# 29_SmartSensor_HW_PGA_ver_0_0_1_PGA460_v.net
KiCad netlist of a schematic drawn in EAGLE
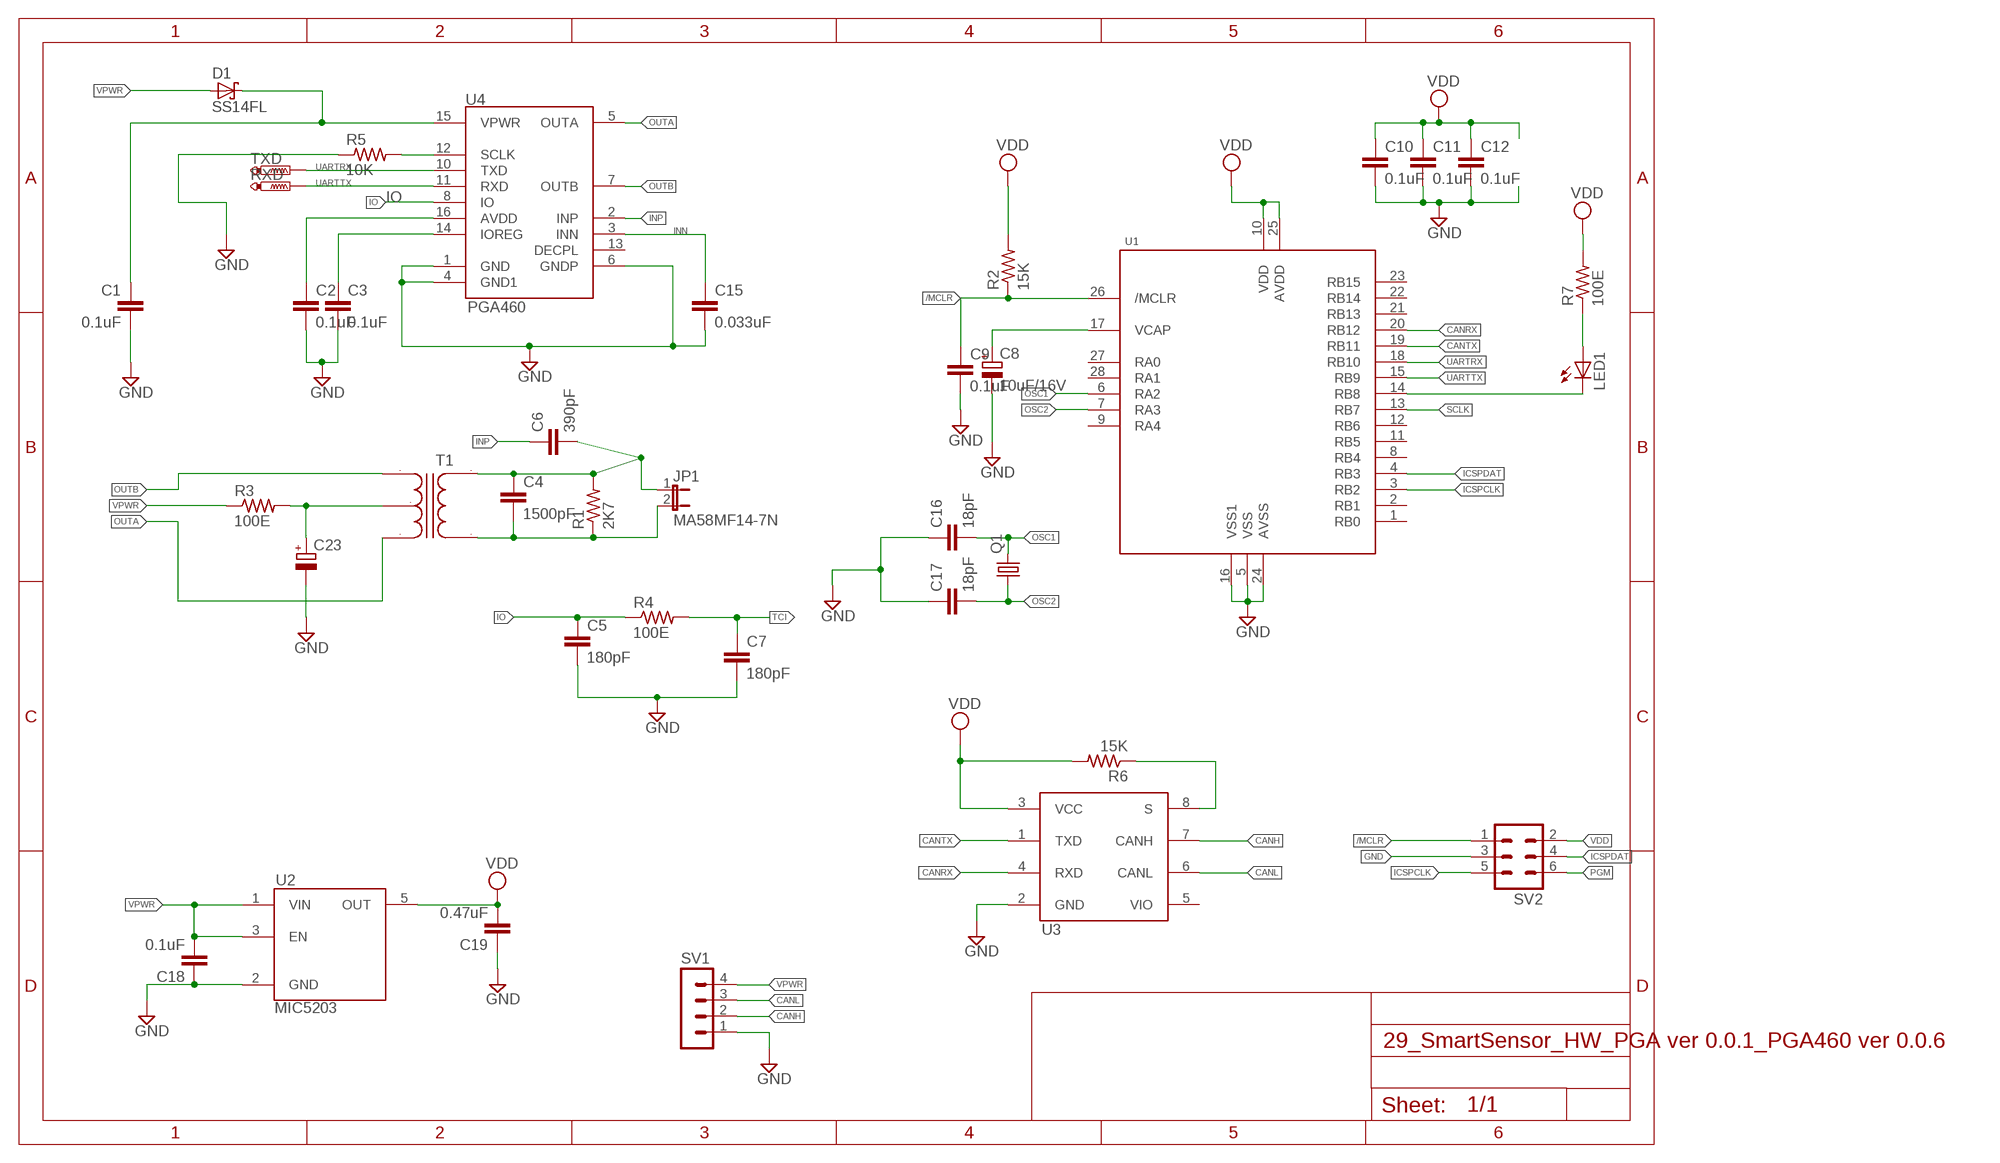
[diagram p0: schematic, sheet 1]

(export (version "E")
  (design (tool "Eeschema 10.0.6"))
  (components
    (comp (ref "C1")
      (value "0.1uF")
      (footprint "eagle-import:C0603K")
      (libsource (lib "eagle-import") (part "C-EUC0603K"))
    )
    (comp (ref "C2")
      (value "0.1uF")
      (footprint "eagle-import:C0603K")
      (libsource (lib "eagle-import") (part "C-EUC0603K"))
    )
    (comp (ref "C3")
      (value "0.1uF")
      (footprint "eagle-import:C0603K")
      (libsource (lib "eagle-import") (part "C-EUC0603K"))
    )
    (comp (ref "C4")
      (value "1500pF")
      (footprint "eagle-import:C0603K")
      (libsource (lib "eagle-import") (part "C-EUC0603K"))
    )
    (comp (ref "C5")
      (value "180pF")
      (footprint "eagle-import:C0603K")
      (libsource (lib "eagle-import") (part "C-EUC0603K"))
    )
    (comp (ref "C6")
      (value "390pF")
      (footprint "eagle-import:C0603K")
      (libsource (lib "eagle-import") (part "C-EUC0603K"))
    )
    (comp (ref "C7")
      (value "180pF")
      (footprint "eagle-import:C0603K")
      (libsource (lib "eagle-import") (part "C-EUC0603K"))
    )
    (comp (ref "C8")
      (value "10uF/16V")
      (footprint "eagle-import:B_3528-21R")
      (libsource (lib "eagle-import") (part "rcl_334_CPOL-EUB/3528-21R"))
    )
    (comp (ref "C9")
      (value "0.1uF")
      (footprint "eagle-import:C0603K")
      (libsource (lib "eagle-import") (part "rcl_334_C-EUC0603K"))
    )
    (comp (ref "C10")
      (value "0.1uF")
      (footprint "eagle-import:C0603K")
      (libsource (lib "eagle-import") (part "rcl_334_C-EUC0603K"))
    )
    (comp (ref "C11")
      (value "0.1uF")
      (footprint "eagle-import:C0603K")
      (libsource (lib "eagle-import") (part "rcl_334_C-EUC0603K"))
    )
    (comp (ref "C12")
      (value "0.1uF")
      (footprint "eagle-import:C0603K")
      (libsource (lib "eagle-import") (part "rcl_334_C-EUC0603K"))
    )
    (comp (ref "C15")
      (value "0.033uF")
      (footprint "eagle-import:C0603K")
      (libsource (lib "eagle-import") (part "C-EUC0603K"))
    )
    (comp (ref "C16")
      (value "18pF")
      (footprint "eagle-import:C0603K")
      (libsource (lib "eagle-import") (part "rcl_334_C-EUC0603K"))
    )
    (comp (ref "C17")
      (value "18pF")
      (footprint "eagle-import:C0603K")
      (libsource (lib "eagle-import") (part "rcl_334_C-EUC0603K"))
    )
    (comp (ref "C18")
      (value "0.1uF")
      (footprint "eagle-import:C0603K")
      (libsource (lib "eagle-import") (part "rcl_334_C-EUC0603K"))
    )
    (comp (ref "C19")
      (value "0.47uF")
      (footprint "eagle-import:C0603K")
      (libsource (lib "eagle-import") (part "rcl_334_C-EUC0603K"))
    )
    (comp (ref "C23")
      (value "CPOL-EUD")
      (footprint "eagle-import:PANASONIC_D")
      (libsource (lib "eagle-import") (part "CPOL-EUD"))
    )
    (comp (ref "D1")
      (value "SS14FL")
      (footprint "eagle-import:SMB")
      (libsource (lib "eagle-import") (part "SCHOTTKY-DIODESMD"))
    )
    (comp (ref "JP1")
      (value "MA58MF14-7N")
      (footprint "eagle-import:JP1")
      (libsource (lib "eagle-import") (part "JP1E"))
    )
    (comp (ref "LED1")
      (value "LEDCHIPLED_0805")
      (footprint "eagle-import:CHIPLED_0805")
      (libsource (lib "eagle-import") (part "LEDCHIPLED_0805"))
    )
    (comp (ref "Q1")
      (value "CRYSTALCTS406")
      (footprint "eagle-import:CTS406")
      (libsource (lib "eagle-import") (part "CRYSTALCTS406"))
    )
    (comp (ref "R1")
      (value "2K7")
      (footprint "eagle-import:R0603")
      (libsource (lib "eagle-import") (part "R-US_R0603"))
    )
    (comp (ref "R2")
      (value "15K")
      (footprint "eagle-import:R0603")
      (libsource (lib "eagle-import") (part "rcl_334_R-US_R0603"))
    )
    (comp (ref "R3")
      (value "100E")
      (footprint "eagle-import:R0603")
      (libsource (lib "eagle-import") (part "R-US_R0603"))
    )
    (comp (ref "R4")
      (value "100E")
      (footprint "eagle-import:R0603")
      (libsource (lib "eagle-import") (part "R-US_R0603"))
    )
    (comp (ref "R5")
      (value "10K")
      (footprint "eagle-import:R0603")
      (libsource (lib "eagle-import") (part "R-US_R0603"))
    )
    (comp (ref "R6")
      (value "15K")
      (footprint "eagle-import:R0603")
      (libsource (lib "eagle-import") (part "rcl_334_R-US_R0603"))
    )
    (comp (ref "R7")
      (value "100E")
      (footprint "eagle-import:R0603")
      (libsource (lib "eagle-import") (part "R-US_R0603"))
    )
    (comp (ref "RXD")
      (value "TXD")
      (footprint "eagle-import:B1,27")
      (libsource (lib "eagle-import") (part "PTR1B1,27"))
    )
    (comp (ref "SV1")
      (value "MA04-1")
      (footprint "eagle-import:MA04-1")
      (libsource (lib "eagle-import") (part "MA04-1"))
    )
    (comp (ref "SV2")
      (value "MA03-2")
      (footprint "eagle-import:MA03-2")
      (libsource (lib "eagle-import") (part "MA03-2"))
    )
    (comp (ref "T1")
      (value "B78416")
      (footprint "eagle-import:B78416")
      (libsource (lib "eagle-import") (part "B78416"))
    )
    (comp (ref "TXD")
      (value "TXD")
      (footprint "eagle-import:B1,27")
      (libsource (lib "eagle-import") (part "PTR1B1,27"))
    )
    (comp (ref "U1")
      (value "DSPIC33EVXXX-28")
      (footprint "eagle-import:QFN65P600X600X100-29T370")
      (libsource (lib "eagle-import") (part "DSPIC33EVXXX-28"))
    )
    (comp (ref "U2")
      (value "MIC5203")
      (footprint "eagle-import:SOT95P280X110-5")
      (libsource (lib "eagle-import") (part "MIC5203"))
    )
    (comp (ref "U3")
      (value "TCAN1051")
      (footprint "eagle-import:SOIC127P599X265-8")
      (libsource (lib "eagle-import") (part "TCAN1051"))
    )
    (comp (ref "U4")
      (value "PGA460")
      (footprint "eagle-import:TSSOP16")
      (libsource (lib "eagle-import") (part "PGA460"))
    )
  )
  (nets
    (net (code "1") (name "/INN") (class "Default")
      (node (ref "C15") (pin "1") (pinfunction "1_1") (pintype "passive"))
      (node (ref "U4") (pin "3") (pinfunction "INN_3") (pintype "bidirectional"))
    )
    (net (code "2") (name "CANH") (class "Default")
      (node (ref "SV1") (pin "2") (pinfunction "2_2") (pintype "passive"))
      (node (ref "U3") (pin "7") (pinfunction "CANH_7") (pintype "bidirectional"))
    )
    (net (code "3") (name "CANL") (class "Default")
      (node (ref "SV1") (pin "3") (pinfunction "3_3") (pintype "passive"))
      (node (ref "U3") (pin "6") (pinfunction "CANL_6") (pintype "bidirectional"))
    )
    (net (code "4") (name "CANRX") (class "Default")
      (node (ref "U1") (pin "20") (pinfunction "RB12_20") (pintype "bidirectional"))
      (node (ref "U3") (pin "4") (pinfunction "RXD_4") (pintype "bidirectional"))
    )
    (net (code "5") (name "CANTX") (class "Default")
      (node (ref "U1") (pin "19") (pinfunction "RB11_19") (pintype "bidirectional"))
      (node (ref "U3") (pin "1") (pinfunction "TXD_1") (pintype "bidirectional"))
    )
    (net (code "6") (name "GND") (class "Default")
      (node (ref "C1") (pin "2") (pinfunction "2_2") (pintype "passive"))
      (node (ref "C10") (pin "2") (pinfunction "2_2") (pintype "passive"))
      (node (ref "C11") (pin "2") (pinfunction "2_2") (pintype "passive"))
      (node (ref "C12") (pin "2") (pinfunction "2_2") (pintype "passive"))
      (node (ref "C15") (pin "2") (pinfunction "2_2") (pintype "passive"))
      (node (ref "C16") (pin "1") (pinfunction "1_1") (pintype "passive"))
      (node (ref "C17") (pin "1") (pinfunction "1_1") (pintype "passive"))
      (node (ref "C18") (pin "1") (pinfunction "1_1") (pintype "passive"))
      (node (ref "C19") (pin "1") (pinfunction "1_1") (pintype "passive"))
      (node (ref "C2") (pin "2") (pinfunction "2_2") (pintype "passive"))
      (node (ref "C23") (pin "-") (pinfunction "-_-") (pintype "passive"))
      (node (ref "C3") (pin "2") (pinfunction "2_2") (pintype "passive"))
      (node (ref "C5") (pin "2") (pinfunction "2_2") (pintype "passive"))
      (node (ref "C7") (pin "2") (pinfunction "2_2") (pintype "passive"))
      (node (ref "C8") (pin "-") (pinfunction "-_-") (pintype "passive"))
      (node (ref "C9") (pin "2") (pinfunction "2_2") (pintype "passive"))
      (node (ref "R5") (pin "1") (pinfunction "1_1") (pintype "passive"))
      (node (ref "SV1") (pin "1") (pinfunction "1_1") (pintype "passive"))
      (node (ref "SV2") (pin "3") (pinfunction "3_3") (pintype "passive"))
      (node (ref "U1") (pin "16") (pinfunction "VSS1_16") (pintype "bidirectional"))
      (node (ref "U1") (pin "24") (pinfunction "AVSS_24") (pintype "bidirectional"))
      (node (ref "U1") (pin "5") (pinfunction "VSS_5") (pintype "bidirectional"))
      (node (ref "U2") (pin "2") (pinfunction "GND_2") (pintype "bidirectional"))
      (node (ref "U3") (pin "2") (pinfunction "GND_2") (pintype "power_in"))
      (node (ref "U4") (pin "1") (pinfunction "GND_1") (pintype "power_in"))
      (node (ref "U4") (pin "4") (pinfunction "GND1_4") (pintype "power_in"))
      (node (ref "U4") (pin "6") (pinfunction "GNDP_6") (pintype "power_in"))
    )
    (net (code "7") (name "ICSPCLK") (class "Default")
      (node (ref "SV2") (pin "5") (pinfunction "5_5") (pintype "passive"))
      (node (ref "U1") (pin "3") (pinfunction "RB2_3") (pintype "bidirectional"))
    )
    (net (code "8") (name "ICSPDAT") (class "Default")
      (node (ref "SV2") (pin "4") (pinfunction "4_4") (pintype "passive"))
      (node (ref "U1") (pin "4") (pinfunction "RB3_4") (pintype "bidirectional"))
    )
    (net (code "9") (name "INP") (class "Default")
      (node (ref "C6") (pin "1") (pinfunction "1_1") (pintype "passive"))
      (node (ref "U4") (pin "2") (pinfunction "INP_2") (pintype "bidirectional"))
    )
    (net (code "10") (name "IO") (class "Default")
      (node (ref "C5") (pin "1") (pinfunction "1_1") (pintype "passive"))
      (node (ref "R4") (pin "1") (pinfunction "1_1") (pintype "passive"))
      (node (ref "U4") (pin "8") (pinfunction "IO_8") (pintype "bidirectional"))
    )
    (net (code "11") (name "Net-(C4-Pad1)") (class "Default")
      (node (ref "C4") (pin "1") (pinfunction "1_1") (pintype "passive"))
      (node (ref "C6") (pin "2") (pinfunction "2_2") (pintype "passive"))
      (node (ref "JP1") (pin "1") (pinfunction "1_1") (pintype "passive"))
      (node (ref "R1") (pin "2") (pinfunction "2_2") (pintype "passive"))
      (node (ref "T1") (pin "6") (pinfunction "6_6") (pintype "passive"))
    )
    (net (code "12") (name "Net-(C4-Pad2)") (class "Default")
      (node (ref "C4") (pin "2") (pinfunction "2_2") (pintype "passive"))
      (node (ref "JP1") (pin "2") (pinfunction "2_2") (pintype "passive"))
      (node (ref "R1") (pin "1") (pinfunction "1_1") (pintype "passive"))
      (node (ref "T1") (pin "4") (pinfunction "4_4") (pintype "passive"))
    )
    (net (code "13") (name "Net-(C23-Pad+)") (class "Default")
      (node (ref "C23") (pin "+") (pinfunction "+_+") (pintype "passive"))
      (node (ref "R3") (pin "2") (pinfunction "2_2") (pintype "passive"))
      (node (ref "T1") (pin "2") (pinfunction "2_2") (pintype "passive"))
    )
    (net (code "14") (name "Net-(LED1-PadA)") (class "Default")
      (node (ref "LED1") (pin "A") (pinfunction "A_A") (pintype "passive"))
      (node (ref "R7") (pin "1") (pinfunction "1_1") (pintype "passive"))
    )
    (net (code "15") (name "Net-(U1-RB8)") (class "Default")
      (node (ref "LED1") (pin "C") (pinfunction "C_C") (pintype "passive"))
      (node (ref "U1") (pin "14") (pinfunction "RB8_14") (pintype "bidirectional"))
    )
    (net (code "16") (name "Net-(U1-VCAP)") (class "Default")
      (node (ref "C8") (pin "+") (pinfunction "+_+") (pintype "passive"))
      (node (ref "U1") (pin "17") (pinfunction "VCAP_17") (pintype "bidirectional"))
    )
    (net (code "17") (name "Net-(U3-S)") (class "Default")
      (node (ref "R6") (pin "1") (pinfunction "1_1") (pintype "passive"))
      (node (ref "U3") (pin "8") (pinfunction "S_8") (pintype "bidirectional"))
    )
    (net (code "18") (name "Net-(U4-AVDD)") (class "Default")
      (node (ref "C2") (pin "1") (pinfunction "1_1") (pintype "passive"))
      (node (ref "U4") (pin "16") (pinfunction "AVDD_16") (pintype "power_in"))
    )
    (net (code "19") (name "Net-(U4-IOREG)") (class "Default")
      (node (ref "C3") (pin "1") (pinfunction "1_1") (pintype "passive"))
      (node (ref "U4") (pin "14") (pinfunction "IOREG_14") (pintype "bidirectional"))
    )
    (net (code "20") (name "Net-(U4-SCLK)") (class "Default")
      (node (ref "R5") (pin "2") (pinfunction "2_2") (pintype "passive"))
      (node (ref "U4") (pin "12") (pinfunction "SCLK_12") (pintype "bidirectional"))
    )
    (net (code "21") (name "Net-(U4-VPWR)") (class "Default")
      (node (ref "C1") (pin "1") (pinfunction "1_1") (pintype "passive"))
      (node (ref "D1") (pin "C") (pinfunction "C_C") (pintype "passive"))
      (node (ref "U4") (pin "15") (pinfunction "VPWR_15") (pintype "power_in"))
    )
    (net (code "22") (name "OSC1") (class "Default")
      (node (ref "C16") (pin "2") (pinfunction "2_2") (pintype "passive"))
      (node (ref "Q1") (pin "3") (pinfunction "2_3") (pintype "passive"))
      (node (ref "U1") (pin "6") (pinfunction "RA2_6") (pintype "bidirectional"))
    )
    (net (code "23") (name "OSC2") (class "Default")
      (node (ref "C17") (pin "2") (pinfunction "2_2") (pintype "passive"))
      (node (ref "Q1") (pin "1") (pinfunction "1_1") (pintype "passive"))
      (node (ref "U1") (pin "7") (pinfunction "RA3_7") (pintype "bidirectional"))
    )
    (net (code "24") (name "OUTA") (class "Default")
      (node (ref "T1") (pin "3") (pinfunction "3_3") (pintype "passive"))
      (node (ref "U4") (pin "5") (pinfunction "OUTA_5") (pintype "bidirectional"))
    )
    (net (code "25") (name "OUTB") (class "Default")
      (node (ref "T1") (pin "1") (pinfunction "1_1") (pintype "passive"))
      (node (ref "U4") (pin "7") (pinfunction "OUTB_7") (pintype "bidirectional"))
    )
    (net (code "26") (name "PGM") (class "Default")
      (node (ref "SV2") (pin "6") (pinfunction "6_6") (pintype "passive"))
    )
    (net (code "27") (name "SCLK") (class "Default")
      (node (ref "U1") (pin "13") (pinfunction "RB7_13") (pintype "bidirectional"))
    )
    (net (code "28") (name "TCI") (class "Default")
      (node (ref "C7") (pin "1") (pinfunction "1_1") (pintype "passive"))
      (node (ref "R4") (pin "2") (pinfunction "2_2") (pintype "passive"))
    )
    (net (code "29") (name "UARTRX") (class "Default")
      (node (ref "TXD") (pin "TP") (pinfunction "TP_TP") (pintype "input"))
      (node (ref "U1") (pin "18") (pinfunction "RB10_18") (pintype "bidirectional"))
      (node (ref "U4") (pin "10") (pinfunction "TXD_10") (pintype "bidirectional"))
    )
    (net (code "30") (name "UARTTX") (class "Default")
      (node (ref "RXD") (pin "TP") (pinfunction "TP_TP") (pintype "input"))
      (node (ref "U1") (pin "15") (pinfunction "RB9_15") (pintype "bidirectional"))
      (node (ref "U4") (pin "11") (pinfunction "RXD_11") (pintype "bidirectional"))
    )
    (net (code "31") (name "VDD") (class "Default")
      (node (ref "C10") (pin "1") (pinfunction "1_1") (pintype "passive"))
      (node (ref "C11") (pin "1") (pinfunction "1_1") (pintype "passive"))
      (node (ref "C12") (pin "1") (pinfunction "1_1") (pintype "passive"))
      (node (ref "C19") (pin "2") (pinfunction "2_2") (pintype "passive"))
      (node (ref "R2") (pin "2") (pinfunction "2_2") (pintype "passive"))
      (node (ref "R6") (pin "2") (pinfunction "2_2") (pintype "passive"))
      (node (ref "R7") (pin "2") (pinfunction "2_2") (pintype "passive"))
      (node (ref "SV2") (pin "2") (pinfunction "2_2") (pintype "passive"))
      (node (ref "U1") (pin "10") (pinfunction "VDD_10") (pintype "bidirectional"))
      (node (ref "U1") (pin "25") (pinfunction "AVDD_25") (pintype "bidirectional"))
      (node (ref "U2") (pin "5") (pinfunction "OUT_5") (pintype "bidirectional"))
      (node (ref "U3") (pin "3") (pinfunction "VCC_3") (pintype "power_in"))
    )
    (net (code "32") (name "VPWR") (class "Default")
      (node (ref "C18") (pin "2") (pinfunction "2_2") (pintype "passive"))
      (node (ref "D1") (pin "A") (pinfunction "A_A") (pintype "passive"))
      (node (ref "R3") (pin "1") (pinfunction "1_1") (pintype "passive"))
      (node (ref "SV1") (pin "4") (pinfunction "4_4") (pintype "passive"))
      (node (ref "U2") (pin "1") (pinfunction "VIN_1") (pintype "bidirectional"))
      (node (ref "U2") (pin "3") (pinfunction "EN_3") (pintype "bidirectional"))
    )
    (net (code "33") (name "unconnected-(U1-RA0-Pad27)") (class "Default")
      (node (ref "U1") (pin "27") (pinfunction "RA0_27") (pintype "bidirectional"))
    )
    (net (code "34") (name "unconnected-(U1-RA1-Pad28)") (class "Default")
      (node (ref "U1") (pin "28") (pinfunction "RA1_28") (pintype "bidirectional"))
    )
    (net (code "35") (name "unconnected-(U1-RA4-Pad9)") (class "Default")
      (node (ref "U1") (pin "9") (pinfunction "RA4_9") (pintype "bidirectional"))
    )
    (net (code "36") (name "unconnected-(U1-RB0-Pad1)") (class "Default")
      (node (ref "U1") (pin "1") (pinfunction "RB0_1") (pintype "bidirectional"))
    )
    (net (code "37") (name "unconnected-(U1-RB1-Pad2)") (class "Default")
      (node (ref "U1") (pin "2") (pinfunction "RB1_2") (pintype "bidirectional"))
    )
    (net (code "38") (name "unconnected-(U1-RB4-Pad8)") (class "Default")
      (node (ref "U1") (pin "8") (pinfunction "RB4_8") (pintype "bidirectional"))
    )
    (net (code "39") (name "unconnected-(U1-RB5-Pad11)") (class "Default")
      (node (ref "U1") (pin "11") (pinfunction "RB5_11") (pintype "bidirectional"))
    )
    (net (code "40") (name "unconnected-(U1-RB6-Pad12)") (class "Default")
      (node (ref "U1") (pin "12") (pinfunction "RB6_12") (pintype "bidirectional"))
    )
    (net (code "41") (name "unconnected-(U1-RB13-Pad21)") (class "Default")
      (node (ref "U1") (pin "21") (pinfunction "RB13_21") (pintype "bidirectional"))
    )
    (net (code "42") (name "unconnected-(U1-RB14-Pad22)") (class "Default")
      (node (ref "U1") (pin "22") (pinfunction "RB14_22") (pintype "bidirectional"))
    )
    (net (code "43") (name "unconnected-(U1-RB15-Pad23)") (class "Default")
      (node (ref "U1") (pin "23") (pinfunction "RB15_23") (pintype "bidirectional"))
    )
    (net (code "44") (name "unconnected-(U3-VIO-Pad5)") (class "Default")
      (node (ref "U3") (pin "5") (pinfunction "VIO_5") (pintype "bidirectional"))
    )
    (net (code "45") (name "unconnected-(U4-DECPL-Pad13)") (class "Default")
      (node (ref "U4") (pin "13") (pinfunction "DECPL_13") (pintype "bidirectional"))
    )
    (net (code "46") (name "{slash}MCLR") (class "Default")
      (node (ref "C9") (pin "1") (pinfunction "1_1") (pintype "passive"))
      (node (ref "R2") (pin "1") (pinfunction "1_1") (pintype "passive"))
      (node (ref "SV2") (pin "1") (pinfunction "1_1") (pintype "passive"))
      (node (ref "U1") (pin "26") (pinfunction "/MCLR_26") (pintype "bidirectional"))
    )
  )
)
